# PCB_EnergyMonitor_SMT.net
KiCad netlist of a schematic drawn in Altium Designer
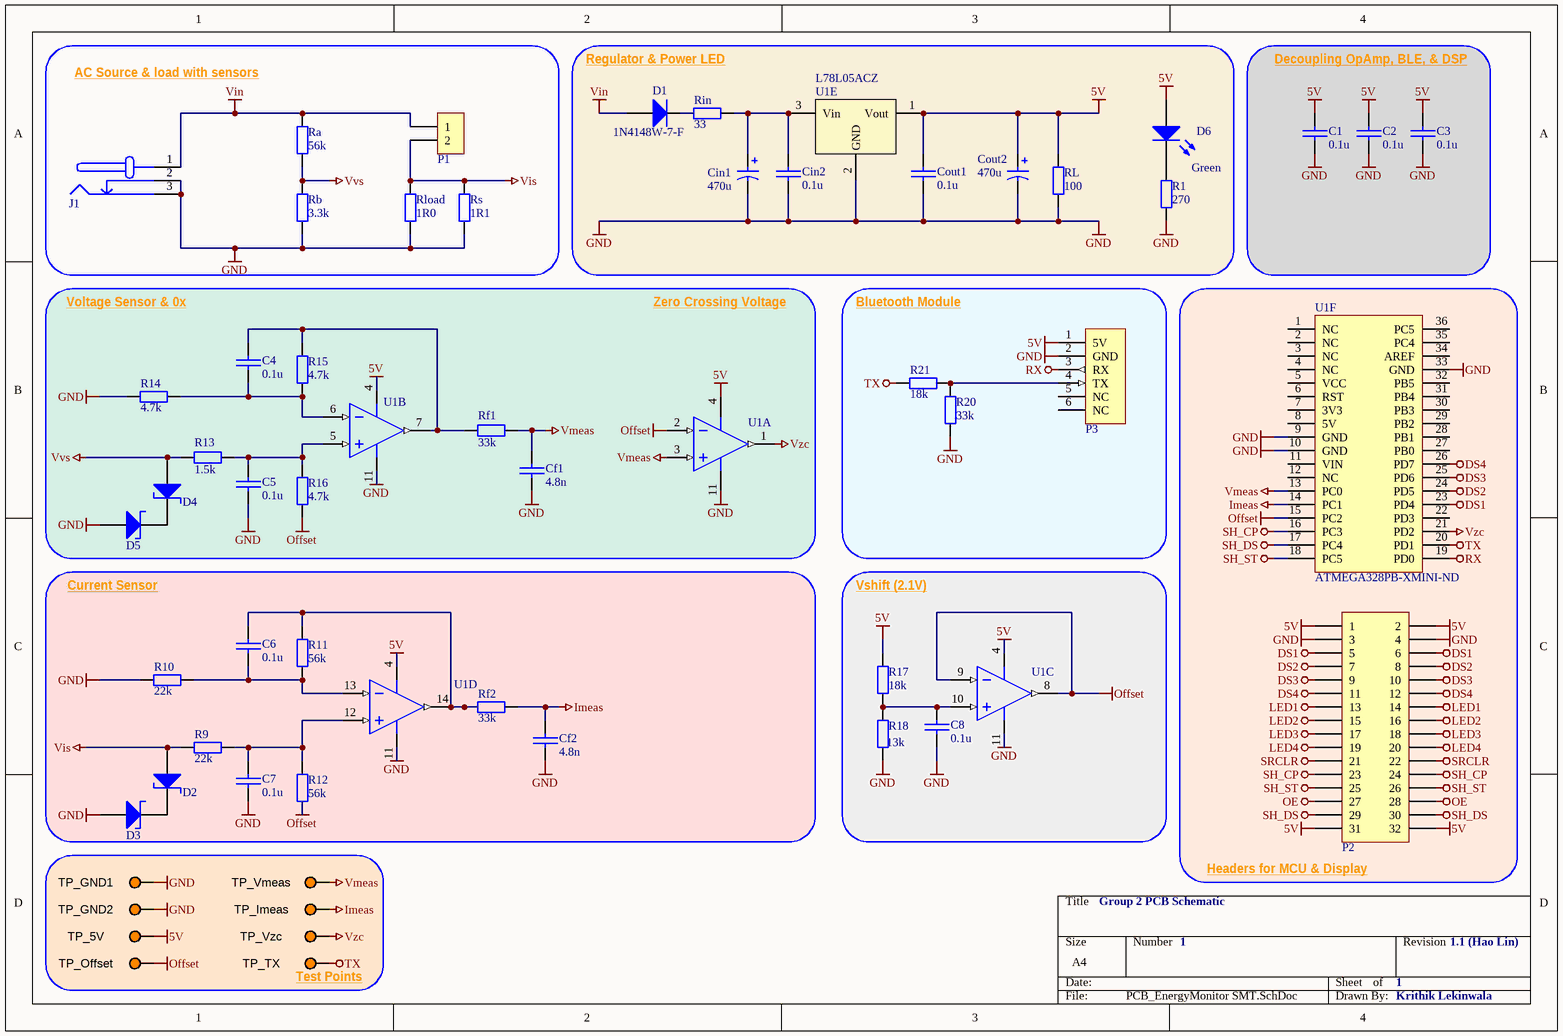
[diagram p0: PCB_EnergyMonitor SMT.SchDoc]

(export (version "E")
  (design (tool "Eeschema 10.0.6"))
  (components
    (comp (ref "C1")
      (value "0.1u")
      (footprint "0805 CAP")
      (description "SMT ceramic capacitor 0805 size")
      (libsource (lib "EE209_Library") (part "CerCap_SMT_0805"))
    )
    (comp (ref "C2")
      (value "0.1u")
      (footprint "0805 CAP")
      (description "SMT ceramic capacitor 0805 size")
      (libsource (lib "EE209_Library") (part "CerCap_SMT_0805"))
    )
    (comp (ref "C3")
      (value "0.1u")
      (footprint "0805 CAP")
      (description "SMT ceramic capacitor 0805 size")
      (libsource (lib "EE209_Library") (part "CerCap_SMT_0805"))
    )
    (comp (ref "C4")
      (value "0.1u")
      (footprint "0805 CAP")
      (description "SMT ceramic capacitor 0805 size")
      (libsource (lib "EE209_Library") (part "CerCap_SMT_0805"))
    )
    (comp (ref "C5")
      (value "0.1u")
      (footprint "0805 CAP")
      (description "SMT ceramic capacitor 0805 size")
      (libsource (lib "EE209_Library") (part "CerCap_SMT_0805"))
    )
    (comp (ref "C6")
      (value "0.1u")
      (footprint "0805 CAP")
      (description "SMT ceramic capacitor 0805 size")
      (libsource (lib "EE209_Library") (part "CerCap_SMT_0805"))
    )
    (comp (ref "C7")
      (value "0.1u")
      (footprint "0805 CAP")
      (description "SMT ceramic capacitor 0805 size")
      (libsource (lib "EE209_Library") (part "CerCap_SMT_0805"))
    )
    (comp (ref "C8")
      (value "0.1u")
      (footprint "0805 CAP")
      (description "SMT ceramic capacitor 0805 size")
      (libsource (lib "EE209_Library") (part "CerCap_SMT_0805"))
    )
    (comp (ref "Cf1")
      (value "4.8n")
      (footprint "0805 CAP")
      (description "SMT ceramic capacitor 0805 size")
      (libsource (lib "EE209_Library") (part "CerCap_SMT_0805"))
    )
    (comp (ref "Cf2")
      (value "4.8n")
      (footprint "0805 CAP")
      (description "SMT ceramic capacitor 0805 size")
      (libsource (lib "EE209_Library") (part "CerCap_SMT_0805"))
    )
    (comp (ref "Cin1")
      (value "470u")
      (footprint "CAP POL 8x5.4mm SMT")
      (description "CAP ALUM 22UF 20% 50V SMD (Model: UWX1H220MCL1GB)")
      (fields
        (field (name "MANUFACTURER") "Nichicon")
        (field (name "MANUFACTURER PART NUMBER") "UWX1V220MCL1GB")
      )
      (libsource (lib "EE209_Library") (part "ElecCap_SMT_8D0"))
    )
    (comp (ref "Cin2")
      (value "0.1u")
      (footprint "0805 CAP")
      (description "SMT ceramic capacitor 0805 size")
      (libsource (lib "EE209_Library") (part "CerCap_SMT_0805"))
    )
    (comp (ref "Cout1")
      (value "0.1u")
      (footprint "0805 CAP")
      (description "SMT ceramic capacitor 0805 size")
      (libsource (lib "EE209_Library") (part "CerCap_SMT_0805"))
    )
    (comp (ref "Cout2")
      (value "470u")
      (footprint "CAP POL 8x5.4mm SMT")
      (description "CAP ALUM 22UF 20% 50V SMD (Model: UWX1H220MCL1GB)")
      (fields
        (field (name "MANUFACTURER") "Nichicon")
        (field (name "MANUFACTURER PART NUMBER") "UWX1V220MCL1GB")
      )
      (libsource (lib "EE209_Library") (part "ElecCap_SMT_8D0"))
    )
    (comp (ref "D1")
      (value "1N4148W-7-F")
      (footprint "SOD123")
      (description "DIODE GEN PURP 100V 300MA SOD123")
      (fields
        (field (name "MANUFACTURER") "Diodes Incorporated")
        (field (name "MANUFACTURER PART NUMBER") "1N4148W-13-F")
      )
      (libsource (lib "EE209_Library") (part "1N4148_SMT_SOD123"))
    )
    (comp (ref "D2")
      (value "BZT52H-B4V7")
      (footprint "SOD123")
      (description "SMT zener diode with SOD123 package")
      (fields
        (field (name "MANUFACTURER") "Nexperia USA Inc.")
        (field (name "MANUFACTURER PART NUMBER") "BZT52H-B4V7,115")
      )
      (libsource (lib "EE209_Library") (part "Zener_SMT_SOD123"))
    )
    (comp (ref "D3")
      (value "BZT52H-B4V7")
      (footprint "SOD123")
      (description "SMT zener diode with SOD123 package")
      (fields
        (field (name "MANUFACTURER") "Nexperia USA Inc.")
        (field (name "MANUFACTURER PART NUMBER") "BZT52H-B4V7,115")
      )
      (libsource (lib "EE209_Library") (part "Zener_SMT_SOD123"))
    )
    (comp (ref "D4")
      (value "BZT52H-B4V7")
      (footprint "SOD123")
      (description "SMT zener diode with SOD123 package")
      (fields
        (field (name "MANUFACTURER") "Nexperia USA Inc.")
        (field (name "MANUFACTURER PART NUMBER") "BZT52H-B4V7,115")
      )
      (libsource (lib "EE209_Library") (part "Zener_SMT_SOD123"))
    )
    (comp (ref "D5")
      (value "BZT52H-B4V7")
      (footprint "SOD123")
      (description "SMT zener diode with SOD123 package")
      (fields
        (field (name "MANUFACTURER") "Nexperia USA Inc.")
        (field (name "MANUFACTURER PART NUMBER") "BZT52H-B4V7,115")
      )
      (libsource (lib "EE209_Library") (part "Zener_SMT_SOD123"))
    )
    (comp (ref "D6")
      (value "Green")
      (footprint "0805 LED")
      (description "SMT LED 0805 size")
      (fields
        (field (name "MANUFACTURER") "Lite-On Inc.")
        (field (name "MANUFACTURER PART NUMBER") "LTST-C170KGKT")
      )
      (libsource (lib "EE209_Library") (part "LED_SMT_0805"))
    )
    (comp (ref "J1")
      (value "DC barrel jack")
      (footprint "AC-Socket")
      (description "DC barrel jack connection to AC source")
      (libsource (lib "EE209_Library") (part "AC_Input"))
    )
    (comp (ref "P1")
      (value "Dual Banana Plugs")
      (footprint "Dual Banana Plug")
      (description "Dual banana plugs connection to the AC load")
      (fields (field (name "PUBLISHER") "Altium Limited"))
      (libsource (lib "EE209_Library") (part "AC_Output"))
    )
    (comp (ref "P2")
      (value "Display")
      (footprint "Display")
      (description "16-Pin Header Connecting Display")
      (libsource (lib "EE209_Library") (part "Display"))
    )
    (comp (ref "P3")
      (value "BLE Module Header")
      (footprint "HM10_HDR1X6")
      (description "2.54mm pitch 6-pin header for BLE module")
      (fields (field (name "PUBLISHER") "Altium Limited"))
      (libsource (lib "EE209_Library") (part "BLEModule_TH"))
    )
    (comp (ref "R1")
      (value "270")
      (footprint "0805 RES")
      (description "0805 resistor")
      (fields (field (name "PUBLISHER") "Altium Limited"))
      (libsource (lib "EE209_Library") (part "Res_SMT_0805"))
    )
    (comp (ref "R9")
      (value "22k")
      (footprint "0805 RES")
      (description "0805 resistor")
      (fields (field (name "PUBLISHER") "Altium Limited"))
      (libsource (lib "") (part "Res_SMT_0805_3"))
    )
    (comp (ref "R10")
      (value "22k")
      (footprint "0805 RES")
      (description "0805 resistor")
      (fields (field (name "PUBLISHER") "Altium Limited"))
      (libsource (lib "") (part "Res_SMT_0805_3"))
    )
    (comp (ref "R11")
      (value "56k")
      (footprint "0805 RES")
      (description "0805 resistor")
      (fields (field (name "PUBLISHER") "Altium Limited"))
      (libsource (lib "EE209_Library") (part "Res_SMT_0805"))
    )
    (comp (ref "R12")
      (value "56k")
      (footprint "0805 RES")
      (description "0805 resistor")
      (fields (field (name "PUBLISHER") "Altium Limited"))
      (libsource (lib "EE209_Library") (part "Res_SMT_0805"))
    )
    (comp (ref "R13")
      (value "1.5k")
      (footprint "0805 RES")
      (description "0805 resistor")
      (fields (field (name "PUBLISHER") "Altium Limited"))
      (libsource (lib "") (part "Res_SMT_0805_3"))
    )
    (comp (ref "R14")
      (value "4.7k")
      (footprint "0805 RES")
      (description "0805 resistor")
      (fields (field (name "PUBLISHER") "Altium Limited"))
      (libsource (lib "") (part "Res_SMT_0805_3"))
    )
    (comp (ref "R15")
      (value "4.7k")
      (footprint "0805 RES")
      (description "0805 resistor")
      (fields (field (name "PUBLISHER") "Altium Limited"))
      (libsource (lib "EE209_Library") (part "Res_SMT_0805"))
    )
    (comp (ref "R16")
      (value "4.7k")
      (footprint "0805 RES")
      (description "0805 resistor")
      (fields (field (name "PUBLISHER") "Altium Limited"))
      (libsource (lib "EE209_Library") (part "Res_SMT_0805"))
    )
    (comp (ref "R17")
      (value "18k")
      (footprint "0805 RES")
      (description "0805 resistor")
      (fields (field (name "PUBLISHER") "Altium Limited"))
      (libsource (lib "EE209_Library") (part "Res_SMT_0805"))
    )
    (comp (ref "R18")
      (value "13k")
      (footprint "0805 RES")
      (description "0805 resistor")
      (fields (field (name "PUBLISHER") "Altium Limited"))
      (libsource (lib "EE209_Library") (part "Res_SMT_0805"))
    )
    (comp (ref "R20")
      (value "33k")
      (footprint "0805 RES")
      (description "0805 resistor")
      (fields (field (name "PUBLISHER") "Altium Limited"))
      (libsource (lib "EE209_Library") (part "Res_SMT_0805"))
    )
    (comp (ref "R21")
      (value "18k")
      (footprint "0805 RES")
      (description "0805 resistor")
      (fields (field (name "PUBLISHER") "Altium Limited"))
      (libsource (lib "") (part "Res_SMT_0805_2"))
    )
    (comp (ref "Ra")
      (value "56k")
      (footprint "0805 RES")
      (description "0805 resistor")
      (fields (field (name "PUBLISHER") "Altium Limited"))
      (libsource (lib "EE209_Library") (part "Res_SMT_0805"))
    )
    (comp (ref "Rb")
      (value "3.3k")
      (footprint "0805 RES")
      (description "0805 resistor")
      (fields (field (name "PUBLISHER") "Altium Limited"))
      (libsource (lib "EE209_Library") (part "Res_SMT_0805"))
    )
    (comp (ref "Rf1")
      (value "33k")
      (footprint "0805 RES")
      (description "0805 resistor")
      (fields (field (name "PUBLISHER") "Altium Limited"))
      (libsource (lib "") (part "Res_SMT_0805_3"))
    )
    (comp (ref "Rf2")
      (value "33k")
      (footprint "0805 RES")
      (description "0805 resistor")
      (fields (field (name "PUBLISHER") "Altium Limited"))
      (libsource (lib "") (part "Res_SMT_0805_3"))
    )
    (comp (ref "Rin")
      (value "33")
      (footprint "0805 RES")
      (description "0805 resistor")
      (fields (field (name "PUBLISHER") "Altium Limited"))
      (libsource (lib "") (part "Res_SMT_0805_3"))
    )
    (comp (ref "RL")
      (value "100")
      (footprint "0805 RES")
      (description "0805 resistor")
      (fields (field (name "PUBLISHER") "Altium Limited"))
      (libsource (lib "EE209_Library") (part "Res_SMT_0805"))
    )
    (comp (ref "Rload")
      (value "1R0")
      (footprint "0805 RES")
      (description "0805 resistor")
      (fields (field (name "PUBLISHER") "Altium Limited"))
      (libsource (lib "EE209_Library") (part "Res_SMT_0805"))
    )
    (comp (ref "Rs")
      (value "1R1")
      (footprint "0805 RES")
      (description "0805 resistor")
      (fields (field (name "PUBLISHER") "Altium Limited"))
      (libsource (lib "") (part "Res_SMT_0805_1"))
    )
    (comp (ref "TP_5V")
      (value "5003")
      (footprint "TP_TH")
      (description "Test Point, Orange, 1-Pin THD, RoHS")
      (libsource (lib "EE209_Library") (part "TestPoint"))
    )
    (comp (ref "TP_GND1")
      (value "5003")
      (footprint "TP_TH")
      (description "Test Point, Orange, 1-Pin THD, RoHS")
      (libsource (lib "EE209_Library") (part "TestPoint"))
    )
    (comp (ref "TP_GND2")
      (value "5003")
      (footprint "TP_TH")
      (description "Test Point, Orange, 1-Pin THD, RoHS")
      (libsource (lib "EE209_Library") (part "TestPoint"))
    )
    (comp (ref "TP_Imeas")
      (value "5003")
      (footprint "TP_TH")
      (description "Test Point, Orange, 1-Pin THD, RoHS")
      (libsource (lib "EE209_Library") (part "TestPoint"))
    )
    (comp (ref "TP_Offset")
      (value "5003")
      (footprint "TP_TH")
      (description "Test Point, Orange, 1-Pin THD, RoHS")
      (libsource (lib "EE209_Library") (part "TestPoint"))
    )
    (comp (ref "TP_TX")
      (value "5003")
      (footprint "TP_TH")
      (description "Test Point, Orange, 1-Pin THD, RoHS")
      (libsource (lib "EE209_Library") (part "TestPoint"))
    )
    (comp (ref "TP_Vmeas")
      (value "5003")
      (footprint "TP_TH")
      (description "Test Point, Orange, 1-Pin THD, RoHS")
      (libsource (lib "EE209_Library") (part "TestPoint"))
    )
    (comp (ref "TP_Vzc")
      (value "5003")
      (footprint "TP_TH")
      (description "Test Point, Orange, 1-Pin THD, RoHS")
      (libsource (lib "EE209_Library") (part "TestPoint"))
    )
    (comp (ref "U1")
      (value "LM324")
      (footprint "DIP-14")
      (description "IC OPAMP GP 14DIP")
      (fields
        (field (name "MANUFACTURER") "ON Semiconductor")
        (field (name "MANUFACTURER PART NUMBER") "LM324N")
      )
      (libsource (lib "EE209_Library") (part "LM324N_TH_DIP16"))
    )
    (comp (ref "U1E")
      (value "L78L05ACZ")
      (footprint "TO-92")
      (description "Voltage Regulator 5V")
      (fields
        (field (name "MANUFACTURER") "ON Semiconductor")
        (field (name "MANUFACTURER PART NUMBER") "LM78L05ACZX")
      )
      (libsource (lib "EE209_Library") (part "L78L05_TH_TO92"))
    )
    (comp (ref "U1F")
      (value "ATmega328PB Xplained Mini Header")
      (footprint "ATmeg328P Xplained")
      (description "Dual 18-pin headers connecting to ATmega328PB Xplained Mini")
      (fields
        (field (name "MANUFACTURER") "Microchip Technology")
        (field (name "MANUFACTURER PART NUMBER") "ATMEGA328PB-XMINI")
        (field (name "SUPPLIER PART NUMBER 1") "ATMEGA328PB-XMINI-ND")
      )
      (libsource (lib "EE209_Library") (part "ATmega328PBXplained_TH"))
    )
  )
  (nets
    (net (code "1") (name "5V") (class "Default")
      (node (ref "C1") (pin "1") (pinfunction "1_1") (pintype "passive"))
      (node (ref "C2") (pin "1") (pinfunction "1_1") (pintype "passive"))
      (node (ref "C3") (pin "1") (pinfunction "1_1") (pintype "passive"))
      (node (ref "Cout1") (pin "1") (pinfunction "1_1") (pintype "passive"))
      (node (ref "Cout2") (pin "1") (pinfunction "1_1") (pintype "passive"))
      (node (ref "D6") (pin "1") (pinfunction "A_1") (pintype "passive"))
      (node (ref "P2") (pin "1") (pinfunction "1_1") (pintype "passive"))
      (node (ref "P2") (pin "2") (pinfunction "2_2") (pintype "passive"))
      (node (ref "P2") (pin "31") (pinfunction "31_31") (pintype "passive"))
      (node (ref "P2") (pin "32") (pinfunction "32_32") (pintype "passive"))
      (node (ref "P3") (pin "1") (pinfunction "5V_1") (pintype "passive"))
      (node (ref "R17") (pin "2") (pinfunction "2_2") (pintype "passive"))
      (node (ref "RL") (pin "2") (pinfunction "2_2") (pintype "passive"))
      (node (ref "TP_5V") (pin "1") (pinfunction "1_1") (pintype "passive"))
      (node (ref "U1") (pin "4") (pinfunction "VDD_4") (pintype "power_in"))
      (node (ref "U1E") (pin "1") (pinfunction "Vout_1") (pintype "passive"))
    )
    (net (code "2") (name "DS1") (class "Default")
      (node (ref "P2") (pin "5") (pinfunction "5_5") (pintype "passive"))
      (node (ref "P2") (pin "6") (pinfunction "6_6") (pintype "passive"))
      (node (ref "U1F") (pin "23") (pinfunction "PD4_23") (pintype "passive"))
    )
    (net (code "3") (name "DS2") (class "Default")
      (node (ref "P2") (pin "7") (pinfunction "7_7") (pintype "passive"))
      (node (ref "P2") (pin "8") (pinfunction "8_8") (pintype "passive"))
      (node (ref "U1F") (pin "24") (pinfunction "PD5_24") (pintype "passive"))
    )
    (net (code "4") (name "DS3") (class "Default")
      (node (ref "P2") (pin "10") (pinfunction "10_10") (pintype "passive"))
      (node (ref "P2") (pin "9") (pinfunction "9_9") (pintype "passive"))
      (node (ref "U1F") (pin "25") (pinfunction "PD6_25") (pintype "passive"))
    )
    (net (code "5") (name "DS4") (class "Default")
      (node (ref "P2") (pin "11") (pinfunction "11_11") (pintype "passive"))
      (node (ref "P2") (pin "12") (pinfunction "12_12") (pintype "passive"))
      (node (ref "U1F") (pin "26") (pinfunction "PD7_26") (pintype "passive"))
    )
    (net (code "6") (name "GND") (class "Default")
      (node (ref "C1") (pin "2") (pinfunction "2_2") (pintype "passive"))
      (node (ref "C2") (pin "2") (pinfunction "2_2") (pintype "passive"))
      (node (ref "C3") (pin "2") (pinfunction "2_2") (pintype "passive"))
      (node (ref "C5") (pin "2") (pinfunction "2_2") (pintype "passive"))
      (node (ref "C7") (pin "2") (pinfunction "2_2") (pintype "passive"))
      (node (ref "C8") (pin "2") (pinfunction "2_2") (pintype "passive"))
      (node (ref "Cf1") (pin "2") (pinfunction "2_2") (pintype "passive"))
      (node (ref "Cf2") (pin "2") (pinfunction "2_2") (pintype "passive"))
      (node (ref "Cin1") (pin "2") (pinfunction "2_2") (pintype "passive"))
      (node (ref "Cin2") (pin "2") (pinfunction "2_2") (pintype "passive"))
      (node (ref "Cout1") (pin "2") (pinfunction "2_2") (pintype "passive"))
      (node (ref "Cout2") (pin "2") (pinfunction "2_2") (pintype "passive"))
      (node (ref "D3") (pin "1") (pinfunction "A_1") (pintype "passive"))
      (node (ref "D5") (pin "1") (pinfunction "A_1") (pintype "passive"))
      (node (ref "J1") (pin "2") (pinfunction "GND_ALT_2") (pintype "power_in"))
      (node (ref "J1") (pin "3") (pinfunction "GND_3") (pintype "power_in"))
      (node (ref "P2") (pin "3") (pinfunction "3_3") (pintype "passive"))
      (node (ref "P2") (pin "4") (pinfunction "4_4") (pintype "passive"))
      (node (ref "P3") (pin "2") (pinfunction "GND_2") (pintype "passive"))
      (node (ref "R1") (pin "1") (pinfunction "1_1") (pintype "passive"))
      (node (ref "R10") (pin "1") (pinfunction "1_1") (pintype "passive"))
      (node (ref "R14") (pin "1") (pinfunction "1_1") (pintype "passive"))
      (node (ref "R18") (pin "1") (pinfunction "1_1") (pintype "passive"))
      (node (ref "R20") (pin "1") (pinfunction "1_1") (pintype "passive"))
      (node (ref "RL") (pin "1") (pinfunction "1_1") (pintype "passive"))
      (node (ref "Rb") (pin "1") (pinfunction "1_1") (pintype "passive"))
      (node (ref "Rload") (pin "1") (pinfunction "1_1") (pintype "passive"))
      (node (ref "Rs") (pin "2") (pinfunction "2_2") (pintype "passive"))
      (node (ref "TP_GND1") (pin "1") (pinfunction "1_1") (pintype "passive"))
      (node (ref "TP_GND2") (pin "1") (pinfunction "1_1") (pintype "passive"))
      (node (ref "U1") (pin "11") (pinfunction "VSS_11") (pintype "power_in"))
      (node (ref "U1E") (pin "2") (pinfunction "GND_2") (pintype "passive"))
      (node (ref "U1F") (pin "10") (pinfunction "GND_10") (pintype "power_in"))
      (node (ref "U1F") (pin "33") (pinfunction "GND_33") (pintype "passive"))
      (node (ref "U1F") (pin "9") (pinfunction "GND_9") (pintype "power_in"))
    )
    (net (code "7") (name "Imeas") (class "Default")
      (node (ref "Cf2") (pin "1") (pinfunction "1_1") (pintype "passive"))
      (node (ref "Rf2") (pin "2") (pinfunction "2_2") (pintype "passive"))
      (node (ref "TP_Imeas") (pin "1") (pinfunction "1_1") (pintype "passive"))
      (node (ref "U1F") (pin "14") (pinfunction "PC1_14") (pintype "passive"))
    )
    (net (code "8") (name "LED1") (class "Default")
      (node (ref "P2") (pin "13") (pinfunction "13_13") (pintype "passive"))
      (node (ref "P2") (pin "14") (pinfunction "14_14") (pintype "passive"))
    )
    (net (code "9") (name "LED2") (class "Default")
      (node (ref "P2") (pin "15") (pinfunction "15_15") (pintype "passive"))
      (node (ref "P2") (pin "16") (pinfunction "16_16") (pintype "passive"))
    )
    (net (code "10") (name "LED3") (class "Default")
      (node (ref "P2") (pin "17") (pinfunction "17_17") (pintype "passive"))
      (node (ref "P2") (pin "18") (pinfunction "18_18") (pintype "passive"))
    )
    (net (code "11") (name "LED4") (class "Default")
      (node (ref "P2") (pin "19") (pinfunction "19_19") (pintype "passive"))
      (node (ref "P2") (pin "20") (pinfunction "20_20") (pintype "passive"))
    )
    (net (code "12") (name "Net-(D1-K)") (class "Default")
      (node (ref "D1") (pin "2") (pinfunction "K_2") (pintype "passive"))
      (node (ref "Rin") (pin "1") (pinfunction "1_1") (pintype "passive"))
    )
    (net (code "13") (name "Net-(D2-K)") (class "Default")
      (node (ref "D2") (pin "2") (pinfunction "K_2") (pintype "passive"))
      (node (ref "D3") (pin "2") (pinfunction "K_2") (pintype "passive"))
    )
    (net (code "14") (name "Net-(D4-K)") (class "Default")
      (node (ref "D4") (pin "2") (pinfunction "K_2") (pintype "passive"))
      (node (ref "D5") (pin "2") (pinfunction "K_2") (pintype "passive"))
    )
    (net (code "15") (name "Net-(D6-K)") (class "Default")
      (node (ref "D6") (pin "2") (pinfunction "K_2") (pintype "passive"))
      (node (ref "R1") (pin "2") (pinfunction "2_2") (pintype "passive"))
    )
    (net (code "16") (name "Net-(P3-TX)") (class "Default")
      (node (ref "P3") (pin "4") (pinfunction "TX_4") (pintype "input"))
      (node (ref "R20") (pin "2") (pinfunction "2_2") (pintype "passive"))
      (node (ref "R21") (pin "1") (pinfunction "1_1") (pintype "passive"))
    )
    (net (code "17") (name "Net-(U1B-VINB+)") (class "Default")
      (node (ref "C5") (pin "1") (pinfunction "1_1") (pintype "passive"))
      (node (ref "R13") (pin "2") (pinfunction "2_2") (pintype "passive"))
      (node (ref "R16") (pin "2") (pinfunction "2_2") (pintype "passive"))
      (node (ref "U1") (pin "5") (pinfunction "VINB+_5") (pintype "input"))
    )
    (net (code "18") (name "Net-(U1B-VINB-)") (class "Default")
      (node (ref "C4") (pin "2") (pinfunction "2_2") (pintype "passive"))
      (node (ref "R14") (pin "2") (pinfunction "2_2") (pintype "passive"))
      (node (ref "R15") (pin "1") (pinfunction "1_1") (pintype "passive"))
      (node (ref "U1") (pin "6") (pinfunction "VINB-_6") (pintype "input"))
    )
    (net (code "19") (name "Net-(U1B-VOUTB)") (class "Default")
      (node (ref "C4") (pin "1") (pinfunction "1_1") (pintype "passive"))
      (node (ref "R15") (pin "2") (pinfunction "2_2") (pintype "passive"))
      (node (ref "Rf1") (pin "1") (pinfunction "1_1") (pintype "passive"))
      (node (ref "U1") (pin "7") (pinfunction "VOUTB_7") (pintype "output"))
    )
    (net (code "20") (name "Net-(U1C-VINC+)") (class "Default")
      (node (ref "C8") (pin "1") (pinfunction "1_1") (pintype "passive"))
      (node (ref "R17") (pin "1") (pinfunction "1_1") (pintype "passive"))
      (node (ref "R18") (pin "2") (pinfunction "2_2") (pintype "passive"))
      (node (ref "U1") (pin "10") (pinfunction "VINC+_10") (pintype "input"))
    )
    (net (code "21") (name "Net-(U1D-VIND+)") (class "Default")
      (node (ref "C7") (pin "1") (pinfunction "1_1") (pintype "passive"))
      (node (ref "R12") (pin "2") (pinfunction "2_2") (pintype "passive"))
      (node (ref "R9") (pin "2") (pinfunction "2_2") (pintype "passive"))
      (node (ref "U1") (pin "12") (pinfunction "VIND+_12") (pintype "input"))
    )
    (net (code "22") (name "Net-(U1D-VIND-)") (class "Default")
      (node (ref "C6") (pin "2") (pinfunction "2_2") (pintype "passive"))
      (node (ref "R10") (pin "2") (pinfunction "2_2") (pintype "passive"))
      (node (ref "R11") (pin "1") (pinfunction "1_1") (pintype "passive"))
      (node (ref "U1") (pin "13") (pinfunction "VIND-_13") (pintype "input"))
    )
    (net (code "23") (name "Net-(U1D-VOUTD)") (class "Default")
      (node (ref "C6") (pin "1") (pinfunction "1_1") (pintype "passive"))
      (node (ref "R11") (pin "2") (pinfunction "2_2") (pintype "passive"))
      (node (ref "Rf2") (pin "1") (pinfunction "1_1") (pintype "passive"))
      (node (ref "U1") (pin "14") (pinfunction "VOUTD_14") (pintype "output"))
    )
    (net (code "24") (name "Net-(U1E-Vin)") (class "Default")
      (node (ref "Cin1") (pin "1") (pinfunction "1_1") (pintype "passive"))
      (node (ref "Cin2") (pin "1") (pinfunction "1_1") (pintype "passive"))
      (node (ref "Rin") (pin "2") (pinfunction "2_2") (pintype "passive"))
      (node (ref "U1E") (pin "3") (pinfunction "Vin_3") (pintype "passive"))
    )
    (net (code "25") (name "OE") (class "Default")
      (node (ref "P2") (pin "27") (pinfunction "27_27") (pintype "passive"))
      (node (ref "P2") (pin "28") (pinfunction "28_28") (pintype "passive"))
    )
    (net (code "26") (name "Offset") (class "Default")
      (node (ref "R12") (pin "1") (pinfunction "1_1") (pintype "passive"))
      (node (ref "R16") (pin "1") (pinfunction "1_1") (pintype "passive"))
      (node (ref "TP_Offset") (pin "1") (pinfunction "1_1") (pintype "passive"))
      (node (ref "U1") (pin "2") (pinfunction "VINA-_2") (pintype "input"))
      (node (ref "U1") (pin "8") (pinfunction "VOUTC_8") (pintype "output"))
      (node (ref "U1") (pin "9") (pinfunction "VINC-_9") (pintype "input"))
      (node (ref "U1F") (pin "15") (pinfunction "PC2_15") (pintype "passive"))
    )
    (net (code "27") (name "RX") (class "Default")
      (node (ref "P3") (pin "3") (pinfunction "RX_3") (pintype "output"))
      (node (ref "U1F") (pin "19") (pinfunction "PD0_19") (pintype "passive"))
    )
    (net (code "28") (name "SH_CP") (class "Default")
      (node (ref "P2") (pin "23") (pinfunction "23_23") (pintype "passive"))
      (node (ref "P2") (pin "24") (pinfunction "24_24") (pintype "passive"))
      (node (ref "U1F") (pin "16") (pinfunction "PC3_16") (pintype "passive"))
    )
    (net (code "29") (name "SH_DS") (class "Default")
      (node (ref "P2") (pin "29") (pinfunction "29_29") (pintype "passive"))
      (node (ref "P2") (pin "30") (pinfunction "30_30") (pintype "passive"))
      (node (ref "U1F") (pin "17") (pinfunction "PC4_17") (pintype "passive"))
    )
    (net (code "30") (name "SH_ST") (class "Default")
      (node (ref "P2") (pin "25") (pinfunction "25_25") (pintype "passive"))
      (node (ref "P2") (pin "26") (pinfunction "26_26") (pintype "passive"))
      (node (ref "U1F") (pin "18") (pinfunction "PC5_18") (pintype "passive"))
    )
    (net (code "31") (name "SRCLR") (class "Default")
      (node (ref "P2") (pin "21") (pinfunction "21_21") (pintype "passive"))
      (node (ref "P2") (pin "22") (pinfunction "22_22") (pintype "passive"))
    )
    (net (code "32") (name "TX") (class "Default")
      (node (ref "R21") (pin "2") (pinfunction "2_2") (pintype "passive"))
      (node (ref "TP_TX") (pin "1") (pinfunction "1_1") (pintype "passive"))
      (node (ref "U1F") (pin "20") (pinfunction "PD1_20") (pintype "passive"))
    )
    (net (code "33") (name "Vin") (class "Default")
      (node (ref "D1") (pin "1") (pinfunction "A_1") (pintype "passive"))
      (node (ref "J1") (pin "1") (pinfunction "VCC_1") (pintype "power_in"))
      (node (ref "P1") (pin "1") (pinfunction "1_1") (pintype "passive"))
      (node (ref "Ra") (pin "2") (pinfunction "2_2") (pintype "passive"))
    )
    (net (code "34") (name "Vis") (class "Default")
      (node (ref "D2") (pin "1") (pinfunction "A_1") (pintype "passive"))
      (node (ref "P1") (pin "2") (pinfunction "2_2") (pintype "passive"))
      (node (ref "R9") (pin "1") (pinfunction "1_1") (pintype "passive"))
      (node (ref "Rload") (pin "2") (pinfunction "2_2") (pintype "passive"))
      (node (ref "Rs") (pin "1") (pinfunction "1_1") (pintype "passive"))
    )
    (net (code "35") (name "Vmeas") (class "Default")
      (node (ref "Cf1") (pin "1") (pinfunction "1_1") (pintype "passive"))
      (node (ref "Rf1") (pin "2") (pinfunction "2_2") (pintype "passive"))
      (node (ref "TP_Vmeas") (pin "1") (pinfunction "1_1") (pintype "passive"))
      (node (ref "U1") (pin "3") (pinfunction "VINA+_3") (pintype "input"))
      (node (ref "U1F") (pin "13") (pinfunction "PC0_13") (pintype "passive"))
    )
    (net (code "36") (name "Vvs") (class "Default")
      (node (ref "D4") (pin "1") (pinfunction "A_1") (pintype "passive"))
      (node (ref "R13") (pin "1") (pinfunction "1_1") (pintype "passive"))
      (node (ref "Ra") (pin "1") (pinfunction "1_1") (pintype "passive"))
      (node (ref "Rb") (pin "2") (pinfunction "2_2") (pintype "passive"))
    )
    (net (code "37") (name "Vzc") (class "Default")
      (node (ref "TP_Vzc") (pin "1") (pinfunction "1_1") (pintype "passive"))
      (node (ref "U1") (pin "1") (pinfunction "VOUTA_1") (pintype "output"))
      (node (ref "U1F") (pin "21") (pinfunction "PD2_21") (pintype "passive"))
    )
    (net (code "38") (name "unconnected-(P3-NC-Pad5)") (class "Default")
      (node (ref "P3") (pin "5") (pinfunction "NC_5") (pintype "passive"))
    )
    (net (code "39") (name "unconnected-(P3-NC-Pad6)") (class "Default")
      (node (ref "P3") (pin "6") (pinfunction "NC_6") (pintype "passive"))
    )
    (net (code "40") (name "unconnected-(U1A-VDD-Pad4)") (class "Default")
      (node (ref "U1") (pin "4") (pinfunction "VDD_4") (pintype "power_in"))
    )
    (net (code "41") (name "unconnected-(U1A-VSS-Pad11)") (class "Default")
      (node (ref "U1") (pin "11") (pinfunction "VSS_11") (pintype "power_in"))
    )
    (net (code "42") (name "unconnected-(U1F-3V3-Pad7)") (class "Default")
      (node (ref "U1F") (pin "7") (pinfunction "3V3_7") (pintype "passive"))
    )
    (net (code "43") (name "unconnected-(U1F-5V-Pad8)") (class "Default")
      (node (ref "U1F") (pin "8") (pinfunction "5V_8") (pintype "power_in"))
    )
    (net (code "44") (name "unconnected-(U1F-AREF-Pad34)") (class "Default")
      (node (ref "U1F") (pin "34") (pinfunction "AREF_34") (pintype "passive"))
    )
    (net (code "45") (name "unconnected-(U1F-NC-Pad1)") (class "Default")
      (node (ref "U1F") (pin "1") (pinfunction "NC_1") (pintype "passive"))
    )
    (net (code "46") (name "unconnected-(U1F-NC-Pad2)") (class "Default")
      (node (ref "U1F") (pin "2") (pinfunction "NC_2") (pintype "passive"))
    )
    (net (code "47") (name "unconnected-(U1F-NC-Pad3)") (class "Default")
      (node (ref "U1F") (pin "3") (pinfunction "NC_3") (pintype "passive"))
    )
    (net (code "48") (name "unconnected-(U1F-NC-Pad4)") (class "Default")
      (node (ref "U1F") (pin "4") (pinfunction "NC_4") (pintype "passive"))
    )
    (net (code "49") (name "unconnected-(U1F-NC-Pad12)") (class "Default")
      (node (ref "U1F") (pin "12") (pinfunction "NC_12") (pintype "passive"))
    )
    (net (code "50") (name "unconnected-(U1F-PB0-Pad27)") (class "Default")
      (node (ref "U1F") (pin "27") (pinfunction "PB0_27") (pintype "passive"))
    )
    (net (code "51") (name "unconnected-(U1F-PB1-Pad28)") (class "Default")
      (node (ref "U1F") (pin "28") (pinfunction "PB1_28") (pintype "passive"))
    )
    (net (code "52") (name "unconnected-(U1F-PB2-Pad29)") (class "Default")
      (node (ref "U1F") (pin "29") (pinfunction "PB2_29") (pintype "passive"))
    )
    (net (code "53") (name "unconnected-(U1F-PB3-Pad30)") (class "Default")
      (node (ref "U1F") (pin "30") (pinfunction "PB3_30") (pintype "passive"))
    )
    (net (code "54") (name "unconnected-(U1F-PB4-Pad31)") (class "Default")
      (node (ref "U1F") (pin "31") (pinfunction "PB4_31") (pintype "passive"))
    )
    (net (code "55") (name "unconnected-(U1F-PB5-Pad32)") (class "Default")
      (node (ref "U1F") (pin "32") (pinfunction "PB5_32") (pintype "passive"))
    )
    (net (code "56") (name "unconnected-(U1F-PC4-Pad35)") (class "Default")
      (node (ref "U1F") (pin "35") (pinfunction "PC4_35") (pintype "passive"))
    )
    (net (code "57") (name "unconnected-(U1F-PC5-Pad36)") (class "Default")
      (node (ref "U1F") (pin "36") (pinfunction "PC5_36") (pintype "passive"))
    )
    (net (code "58") (name "unconnected-(U1F-PD3-Pad22)") (class "Default")
      (node (ref "U1F") (pin "22") (pinfunction "PD3_22") (pintype "passive"))
    )
    (net (code "59") (name "unconnected-(U1F-RST-Pad6)") (class "Default")
      (node (ref "U1F") (pin "6") (pinfunction "RST_6") (pintype "passive"))
    )
    (net (code "60") (name "unconnected-(U1F-VCC-Pad5)") (class "Default")
      (node (ref "U1F") (pin "5") (pinfunction "VCC_5") (pintype "power_in"))
    )
    (net (code "61") (name "unconnected-(U1F-VIN-Pad11)") (class "Default")
      (node (ref "U1F") (pin "11") (pinfunction "VIN_11") (pintype "power_in"))
    )
  )
)
